# ANISMADriverBoard_v02.net
KiCad netlist of a schematic drawn in EAGLE
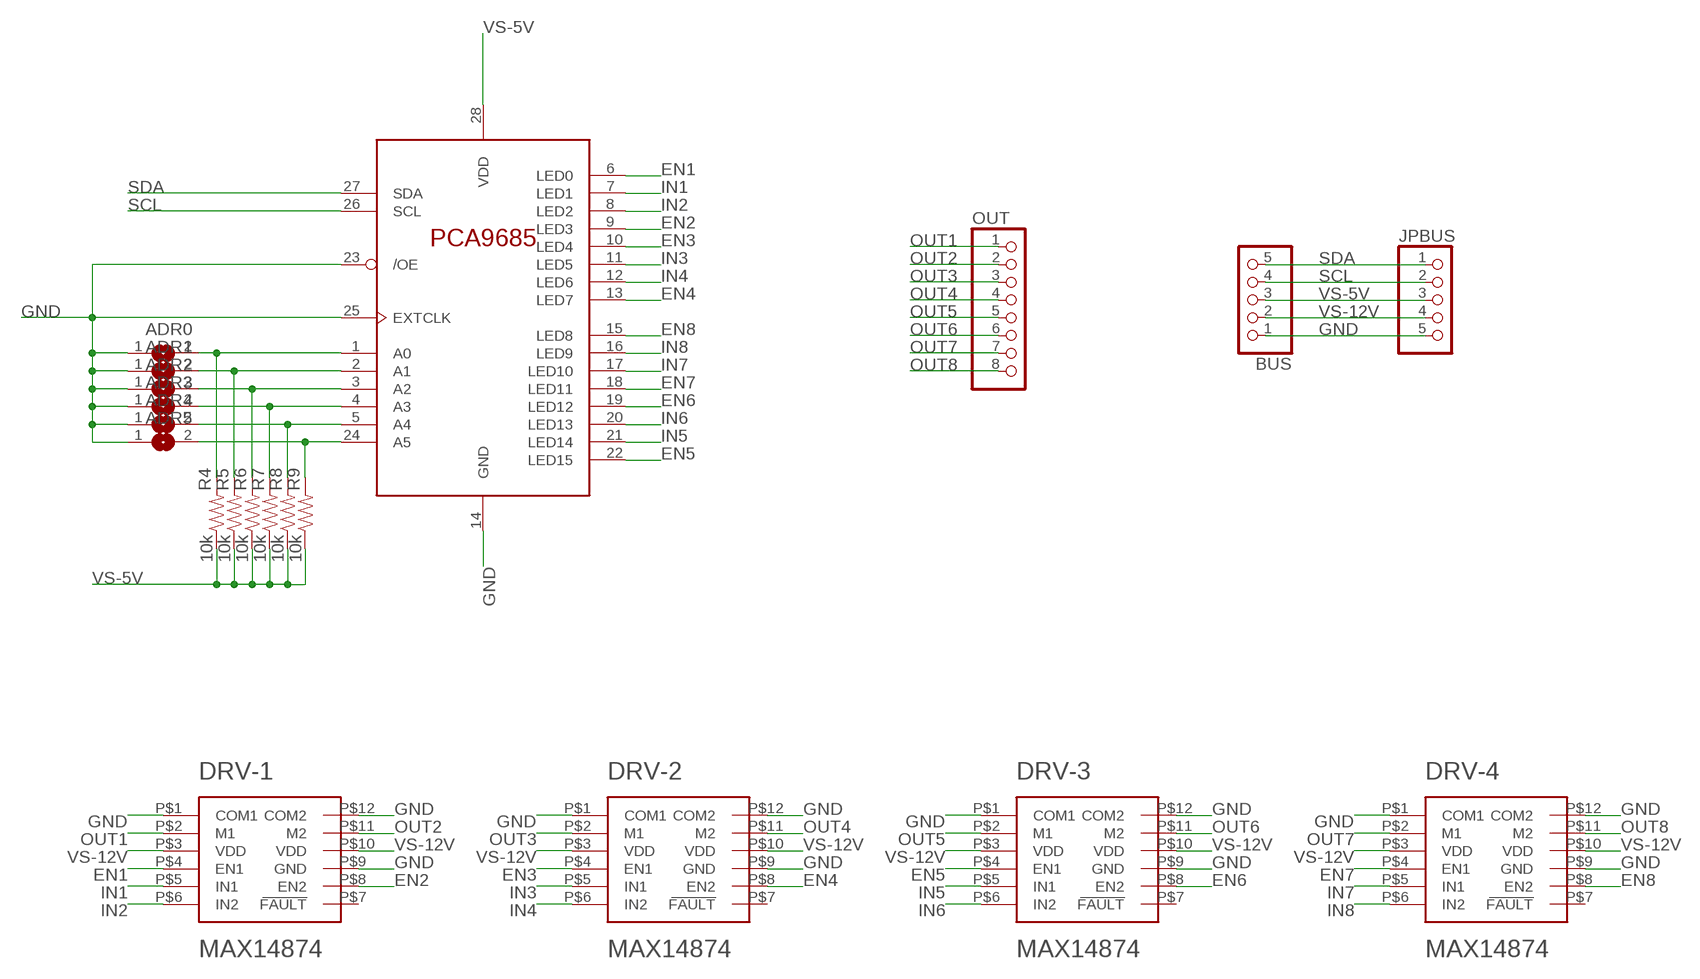
[diagram p0: schematic, sheet 1]

(export (version "E")
  (design (tool "Eeschema 10.0.6"))
  (components
    (comp (ref "ADR0")
      (value "SJ")
      (footprint "eagle-import:SJ")
      (libsource (lib "eagle-import") (part "SJ"))
    )
    (comp (ref "ADR1")
      (value "SJ")
      (footprint "eagle-import:SJ")
      (libsource (lib "eagle-import") (part "SJ"))
    )
    (comp (ref "ADR2")
      (value "SJ")
      (footprint "eagle-import:SJ")
      (libsource (lib "eagle-import") (part "SJ"))
    )
    (comp (ref "ADR3")
      (value "SJ")
      (footprint "eagle-import:SJ")
      (libsource (lib "eagle-import") (part "SJ"))
    )
    (comp (ref "ADR4")
      (value "SJ")
      (footprint "eagle-import:SJ")
      (libsource (lib "eagle-import") (part "SJ"))
    )
    (comp (ref "ADR5")
      (value "SJ")
      (footprint "eagle-import:SJ")
      (libsource (lib "eagle-import") (part "SJ"))
    )
    (comp (ref "BUS")
      (value "PINHD-1X5/90")
      (footprint "eagle-import:1X05_90")
      (libsource (lib "eagle-import") (part "PINHD-1X5/90"))
    )
    (comp (ref "DRV-1")
      (value "MAX14874")
      (footprint "eagle-import:TD1233")
      (libsource (lib "eagle-import") (part "MAX14874"))
    )
    (comp (ref "DRV-2")
      (value "MAX14874")
      (footprint "eagle-import:TD1233")
      (libsource (lib "eagle-import") (part "MAX14874"))
    )
    (comp (ref "DRV-3")
      (value "MAX14874")
      (footprint "eagle-import:TD1233")
      (libsource (lib "eagle-import") (part "MAX14874"))
    )
    (comp (ref "DRV-4")
      (value "MAX14874")
      (footprint "eagle-import:TD1233")
      (libsource (lib "eagle-import") (part "MAX14874"))
    )
    (comp (ref "JPBUS")
      (value "PINHD-1X5/90")
      (footprint "eagle-import:1X05_90")
      (libsource (lib "eagle-import") (part "PINHD-1X5/90"))
    )
    (comp (ref "OUT")
      (value "PINHD-1X8/90")
      (footprint "eagle-import:1X08_90")
      (libsource (lib "eagle-import") (part "PINHD-1X8/90"))
    )
    (comp (ref "PCA9685")
      (value "PCA9685PW")
      (footprint "eagle-import:TSSOP28")
      (libsource (lib "eagle-import") (part "PCA9685PW"))
    )
    (comp (ref "R4")
      (value "10k")
      (footprint "eagle-import:0603")
      (fields (field (name "SPICEPREFIX") "R"))
      (libsource (lib "eagle-import") (part "10KOHM-0603-1/10W-1%"))
    )
    (comp (ref "R5")
      (value "10k")
      (footprint "eagle-import:0603")
      (fields (field (name "SPICEPREFIX") "R"))
      (libsource (lib "eagle-import") (part "10KOHM-0603-1/10W-1%"))
    )
    (comp (ref "R6")
      (value "10k")
      (footprint "eagle-import:0603")
      (fields (field (name "SPICEPREFIX") "R"))
      (libsource (lib "eagle-import") (part "10KOHM-0603-1/10W-1%"))
    )
    (comp (ref "R7")
      (value "10k")
      (footprint "eagle-import:0603")
      (fields (field (name "SPICEPREFIX") "R"))
      (libsource (lib "eagle-import") (part "10KOHM-0603-1/10W-1%"))
    )
    (comp (ref "R8")
      (value "10k")
      (footprint "eagle-import:0603")
      (fields (field (name "SPICEPREFIX") "R"))
      (libsource (lib "eagle-import") (part "10KOHM-0603-1/10W-1%"))
    )
    (comp (ref "R9")
      (value "10k")
      (footprint "eagle-import:0603")
      (fields (field (name "SPICEPREFIX") "R"))
      (libsource (lib "eagle-import") (part "10KOHM-0603-1/10W-1%"))
    )
  )
  (nets
    (net (code "1") (name "/EN1") (class "Default")
      (node (ref "DRV-1") (pin "P$4") (pinfunction "EN1_P$4") (pintype "bidirectional"))
      (node (ref "PCA9685") (pin "6") (pinfunction "LED0_6") (pintype "bidirectional"))
    )
    (net (code "2") (name "/EN2") (class "Default")
      (node (ref "DRV-1") (pin "P$8") (pinfunction "EN2_P$8") (pintype "bidirectional"))
      (node (ref "PCA9685") (pin "9") (pinfunction "LED3_9") (pintype "bidirectional"))
    )
    (net (code "3") (name "/EN3") (class "Default")
      (node (ref "DRV-2") (pin "P$4") (pinfunction "EN1_P$4") (pintype "bidirectional"))
      (node (ref "PCA9685") (pin "10") (pinfunction "LED4_10") (pintype "bidirectional"))
    )
    (net (code "4") (name "/EN4") (class "Default")
      (node (ref "DRV-2") (pin "P$8") (pinfunction "EN2_P$8") (pintype "bidirectional"))
      (node (ref "PCA9685") (pin "13") (pinfunction "LED7_13") (pintype "bidirectional"))
    )
    (net (code "5") (name "/EN5") (class "Default")
      (node (ref "DRV-3") (pin "P$4") (pinfunction "EN1_P$4") (pintype "bidirectional"))
      (node (ref "PCA9685") (pin "22") (pinfunction "LED15_22") (pintype "bidirectional"))
    )
    (net (code "6") (name "/EN6") (class "Default")
      (node (ref "DRV-3") (pin "P$8") (pinfunction "EN2_P$8") (pintype "bidirectional"))
      (node (ref "PCA9685") (pin "19") (pinfunction "LED12_19") (pintype "bidirectional"))
    )
    (net (code "7") (name "/EN7") (class "Default")
      (node (ref "DRV-4") (pin "P$4") (pinfunction "EN1_P$4") (pintype "bidirectional"))
      (node (ref "PCA9685") (pin "18") (pinfunction "LED11_18") (pintype "bidirectional"))
    )
    (net (code "8") (name "/EN8") (class "Default")
      (node (ref "DRV-4") (pin "P$8") (pinfunction "EN2_P$8") (pintype "bidirectional"))
      (node (ref "PCA9685") (pin "15") (pinfunction "LED8_15") (pintype "bidirectional"))
    )
    (net (code "9") (name "/GND") (class "Default")
      (node (ref "ADR0") (pin "1") (pinfunction "1_1") (pintype "passive"))
      (node (ref "ADR1") (pin "1") (pinfunction "1_1") (pintype "passive"))
      (node (ref "ADR2") (pin "1") (pinfunction "1_1") (pintype "passive"))
      (node (ref "ADR3") (pin "1") (pinfunction "1_1") (pintype "passive"))
      (node (ref "ADR4") (pin "1") (pinfunction "1_1") (pintype "passive"))
      (node (ref "ADR5") (pin "1") (pinfunction "1_1") (pintype "passive"))
      (node (ref "BUS") (pin "1") (pinfunction "1_1") (pintype "passive"))
      (node (ref "DRV-1") (pin "P$1") (pinfunction "COM1_P$1") (pintype "bidirectional"))
      (node (ref "DRV-1") (pin "P$12") (pinfunction "COM2_P$12") (pintype "bidirectional"))
      (node (ref "DRV-1") (pin "P$9") (pinfunction "GND_P$9") (pintype "bidirectional"))
      (node (ref "DRV-2") (pin "P$1") (pinfunction "COM1_P$1") (pintype "bidirectional"))
      (node (ref "DRV-2") (pin "P$12") (pinfunction "COM2_P$12") (pintype "bidirectional"))
      (node (ref "DRV-2") (pin "P$9") (pinfunction "GND_P$9") (pintype "bidirectional"))
      (node (ref "DRV-3") (pin "P$1") (pinfunction "COM1_P$1") (pintype "bidirectional"))
      (node (ref "DRV-3") (pin "P$12") (pinfunction "COM2_P$12") (pintype "bidirectional"))
      (node (ref "DRV-3") (pin "P$9") (pinfunction "GND_P$9") (pintype "bidirectional"))
      (node (ref "DRV-4") (pin "P$1") (pinfunction "COM1_P$1") (pintype "bidirectional"))
      (node (ref "DRV-4") (pin "P$12") (pinfunction "COM2_P$12") (pintype "bidirectional"))
      (node (ref "DRV-4") (pin "P$9") (pinfunction "GND_P$9") (pintype "bidirectional"))
      (node (ref "JPBUS") (pin "5") (pinfunction "5_5") (pintype "passive"))
      (node (ref "PCA9685") (pin "14") (pinfunction "GND_14") (pintype "power_in"))
      (node (ref "PCA9685") (pin "23") (pinfunction "/OE_23") (pintype "bidirectional"))
      (node (ref "PCA9685") (pin "25") (pinfunction "EXTCLK_25") (pintype "input"))
    )
    (net (code "10") (name "/IN1") (class "Default")
      (node (ref "DRV-1") (pin "P$5") (pinfunction "IN1_P$5") (pintype "bidirectional"))
      (node (ref "PCA9685") (pin "7") (pinfunction "LED1_7") (pintype "bidirectional"))
    )
    (net (code "11") (name "/IN2") (class "Default")
      (node (ref "DRV-1") (pin "P$6") (pinfunction "IN2_P$6") (pintype "bidirectional"))
      (node (ref "PCA9685") (pin "8") (pinfunction "LED2_8") (pintype "bidirectional"))
    )
    (net (code "12") (name "/IN3") (class "Default")
      (node (ref "DRV-2") (pin "P$5") (pinfunction "IN1_P$5") (pintype "bidirectional"))
      (node (ref "PCA9685") (pin "11") (pinfunction "LED5_11") (pintype "bidirectional"))
    )
    (net (code "13") (name "/IN4") (class "Default")
      (node (ref "DRV-2") (pin "P$6") (pinfunction "IN2_P$6") (pintype "bidirectional"))
      (node (ref "PCA9685") (pin "12") (pinfunction "LED6_12") (pintype "bidirectional"))
    )
    (net (code "14") (name "/IN5") (class "Default")
      (node (ref "DRV-3") (pin "P$5") (pinfunction "IN1_P$5") (pintype "bidirectional"))
      (node (ref "PCA9685") (pin "21") (pinfunction "LED14_21") (pintype "bidirectional"))
    )
    (net (code "15") (name "/IN6") (class "Default")
      (node (ref "DRV-3") (pin "P$6") (pinfunction "IN2_P$6") (pintype "bidirectional"))
      (node (ref "PCA9685") (pin "20") (pinfunction "LED13_20") (pintype "bidirectional"))
    )
    (net (code "16") (name "/IN7") (class "Default")
      (node (ref "DRV-4") (pin "P$5") (pinfunction "IN1_P$5") (pintype "bidirectional"))
      (node (ref "PCA9685") (pin "17") (pinfunction "LED10_17") (pintype "bidirectional"))
    )
    (net (code "17") (name "/IN8") (class "Default")
      (node (ref "DRV-4") (pin "P$6") (pinfunction "IN2_P$6") (pintype "bidirectional"))
      (node (ref "PCA9685") (pin "16") (pinfunction "LED9_16") (pintype "bidirectional"))
    )
    (net (code "18") (name "/OUT1") (class "Default")
      (node (ref "DRV-1") (pin "P$2") (pinfunction "M1_P$2") (pintype "bidirectional"))
      (node (ref "OUT") (pin "1") (pinfunction "1_1") (pintype "passive"))
    )
    (net (code "19") (name "/OUT2") (class "Default")
      (node (ref "DRV-1") (pin "P$11") (pinfunction "M2_P$11") (pintype "bidirectional"))
      (node (ref "OUT") (pin "2") (pinfunction "2_2") (pintype "passive"))
    )
    (net (code "20") (name "/OUT3") (class "Default")
      (node (ref "DRV-2") (pin "P$2") (pinfunction "M1_P$2") (pintype "bidirectional"))
      (node (ref "OUT") (pin "3") (pinfunction "3_3") (pintype "passive"))
    )
    (net (code "21") (name "/OUT4") (class "Default")
      (node (ref "DRV-2") (pin "P$11") (pinfunction "M2_P$11") (pintype "bidirectional"))
      (node (ref "OUT") (pin "4") (pinfunction "4_4") (pintype "passive"))
    )
    (net (code "22") (name "/OUT5") (class "Default")
      (node (ref "DRV-3") (pin "P$2") (pinfunction "M1_P$2") (pintype "bidirectional"))
      (node (ref "OUT") (pin "5") (pinfunction "5_5") (pintype "passive"))
    )
    (net (code "23") (name "/OUT6") (class "Default")
      (node (ref "DRV-3") (pin "P$11") (pinfunction "M2_P$11") (pintype "bidirectional"))
      (node (ref "OUT") (pin "6") (pinfunction "6_6") (pintype "passive"))
    )
    (net (code "24") (name "/OUT7") (class "Default")
      (node (ref "DRV-4") (pin "P$2") (pinfunction "M1_P$2") (pintype "bidirectional"))
      (node (ref "OUT") (pin "7") (pinfunction "7_7") (pintype "passive"))
    )
    (net (code "25") (name "/OUT8") (class "Default")
      (node (ref "DRV-4") (pin "P$11") (pinfunction "M2_P$11") (pintype "bidirectional"))
      (node (ref "OUT") (pin "8") (pinfunction "8_8") (pintype "passive"))
    )
    (net (code "26") (name "/SCL") (class "Default")
      (node (ref "BUS") (pin "4") (pinfunction "4_4") (pintype "passive"))
      (node (ref "JPBUS") (pin "2") (pinfunction "2_2") (pintype "passive"))
      (node (ref "PCA9685") (pin "26") (pinfunction "SCL_26") (pintype "bidirectional"))
    )
    (net (code "27") (name "/SDA") (class "Default")
      (node (ref "BUS") (pin "5") (pinfunction "5_5") (pintype "passive"))
      (node (ref "JPBUS") (pin "1") (pinfunction "1_1") (pintype "passive"))
      (node (ref "PCA9685") (pin "27") (pinfunction "SDA_27") (pintype "bidirectional"))
    )
    (net (code "28") (name "/VS-5V") (class "Default")
      (node (ref "BUS") (pin "3") (pinfunction "3_3") (pintype "passive"))
      (node (ref "JPBUS") (pin "3") (pinfunction "3_3") (pintype "passive"))
      (node (ref "PCA9685") (pin "28") (pinfunction "VDD_28") (pintype "power_in"))
      (node (ref "R4") (pin "1") (pinfunction "1_1") (pintype "passive"))
      (node (ref "R5") (pin "1") (pinfunction "1_1") (pintype "passive"))
      (node (ref "R6") (pin "1") (pinfunction "1_1") (pintype "passive"))
      (node (ref "R7") (pin "1") (pinfunction "1_1") (pintype "passive"))
      (node (ref "R8") (pin "1") (pinfunction "1_1") (pintype "passive"))
      (node (ref "R9") (pin "1") (pinfunction "1_1") (pintype "passive"))
    )
    (net (code "29") (name "/VS-12V") (class "Default")
      (node (ref "BUS") (pin "2") (pinfunction "2_2") (pintype "passive"))
      (node (ref "DRV-1") (pin "P$10") (pinfunction "VDD_P$10") (pintype "bidirectional"))
      (node (ref "DRV-1") (pin "P$3") (pinfunction "VDD_P$3") (pintype "bidirectional"))
      (node (ref "DRV-2") (pin "P$10") (pinfunction "VDD_P$10") (pintype "bidirectional"))
      (node (ref "DRV-2") (pin "P$3") (pinfunction "VDD_P$3") (pintype "bidirectional"))
      (node (ref "DRV-3") (pin "P$10") (pinfunction "VDD_P$10") (pintype "bidirectional"))
      (node (ref "DRV-3") (pin "P$3") (pinfunction "VDD_P$3") (pintype "bidirectional"))
      (node (ref "DRV-4") (pin "P$10") (pinfunction "VDD_P$10") (pintype "bidirectional"))
      (node (ref "DRV-4") (pin "P$3") (pinfunction "VDD_P$3") (pintype "bidirectional"))
      (node (ref "JPBUS") (pin "4") (pinfunction "4_4") (pintype "passive"))
    )
    (net (code "30") (name "Net-(PCA9685-A0)") (class "Default")
      (node (ref "ADR0") (pin "2") (pinfunction "2_2") (pintype "passive"))
      (node (ref "PCA9685") (pin "1") (pinfunction "A0_1") (pintype "bidirectional"))
      (node (ref "R4") (pin "2") (pinfunction "2_2") (pintype "passive"))
    )
    (net (code "31") (name "Net-(PCA9685-A1)") (class "Default")
      (node (ref "ADR1") (pin "2") (pinfunction "2_2") (pintype "passive"))
      (node (ref "PCA9685") (pin "2") (pinfunction "A1_2") (pintype "bidirectional"))
      (node (ref "R5") (pin "2") (pinfunction "2_2") (pintype "passive"))
    )
    (net (code "32") (name "Net-(PCA9685-A2)") (class "Default")
      (node (ref "ADR2") (pin "2") (pinfunction "2_2") (pintype "passive"))
      (node (ref "PCA9685") (pin "3") (pinfunction "A2_3") (pintype "bidirectional"))
      (node (ref "R6") (pin "2") (pinfunction "2_2") (pintype "passive"))
    )
    (net (code "33") (name "Net-(PCA9685-A3)") (class "Default")
      (node (ref "ADR3") (pin "2") (pinfunction "2_2") (pintype "passive"))
      (node (ref "PCA9685") (pin "4") (pinfunction "A3_4") (pintype "bidirectional"))
      (node (ref "R7") (pin "2") (pinfunction "2_2") (pintype "passive"))
    )
    (net (code "34") (name "Net-(PCA9685-A4)") (class "Default")
      (node (ref "ADR4") (pin "2") (pinfunction "2_2") (pintype "passive"))
      (node (ref "PCA9685") (pin "5") (pinfunction "A4_5") (pintype "bidirectional"))
      (node (ref "R8") (pin "2") (pinfunction "2_2") (pintype "passive"))
    )
    (net (code "35") (name "Net-(PCA9685-A5)") (class "Default")
      (node (ref "ADR5") (pin "2") (pinfunction "2_2") (pintype "passive"))
      (node (ref "PCA9685") (pin "24") (pinfunction "A5_24") (pintype "bidirectional"))
      (node (ref "R9") (pin "2") (pinfunction "2_2") (pintype "passive"))
    )
    (net (code "36") (name "unconnected-(DRV-1-FAULT-PadP$7)") (class "Default")
      (node (ref "DRV-1") (pin "P$7") (pinfunction "FAULT_P$7") (pintype "bidirectional"))
    )
    (net (code "37") (name "unconnected-(DRV-2-FAULT-PadP$7)") (class "Default")
      (node (ref "DRV-2") (pin "P$7") (pinfunction "FAULT_P$7") (pintype "bidirectional"))
    )
    (net (code "38") (name "unconnected-(DRV-3-FAULT-PadP$7)") (class "Default")
      (node (ref "DRV-3") (pin "P$7") (pinfunction "FAULT_P$7") (pintype "bidirectional"))
    )
    (net (code "39") (name "unconnected-(DRV-4-FAULT-PadP$7)") (class "Default")
      (node (ref "DRV-4") (pin "P$7") (pinfunction "FAULT_P$7") (pintype "bidirectional"))
    )
  )
)
